# RobotSchematic.net
KiCad netlist of a schematic drawn in EasyEDA
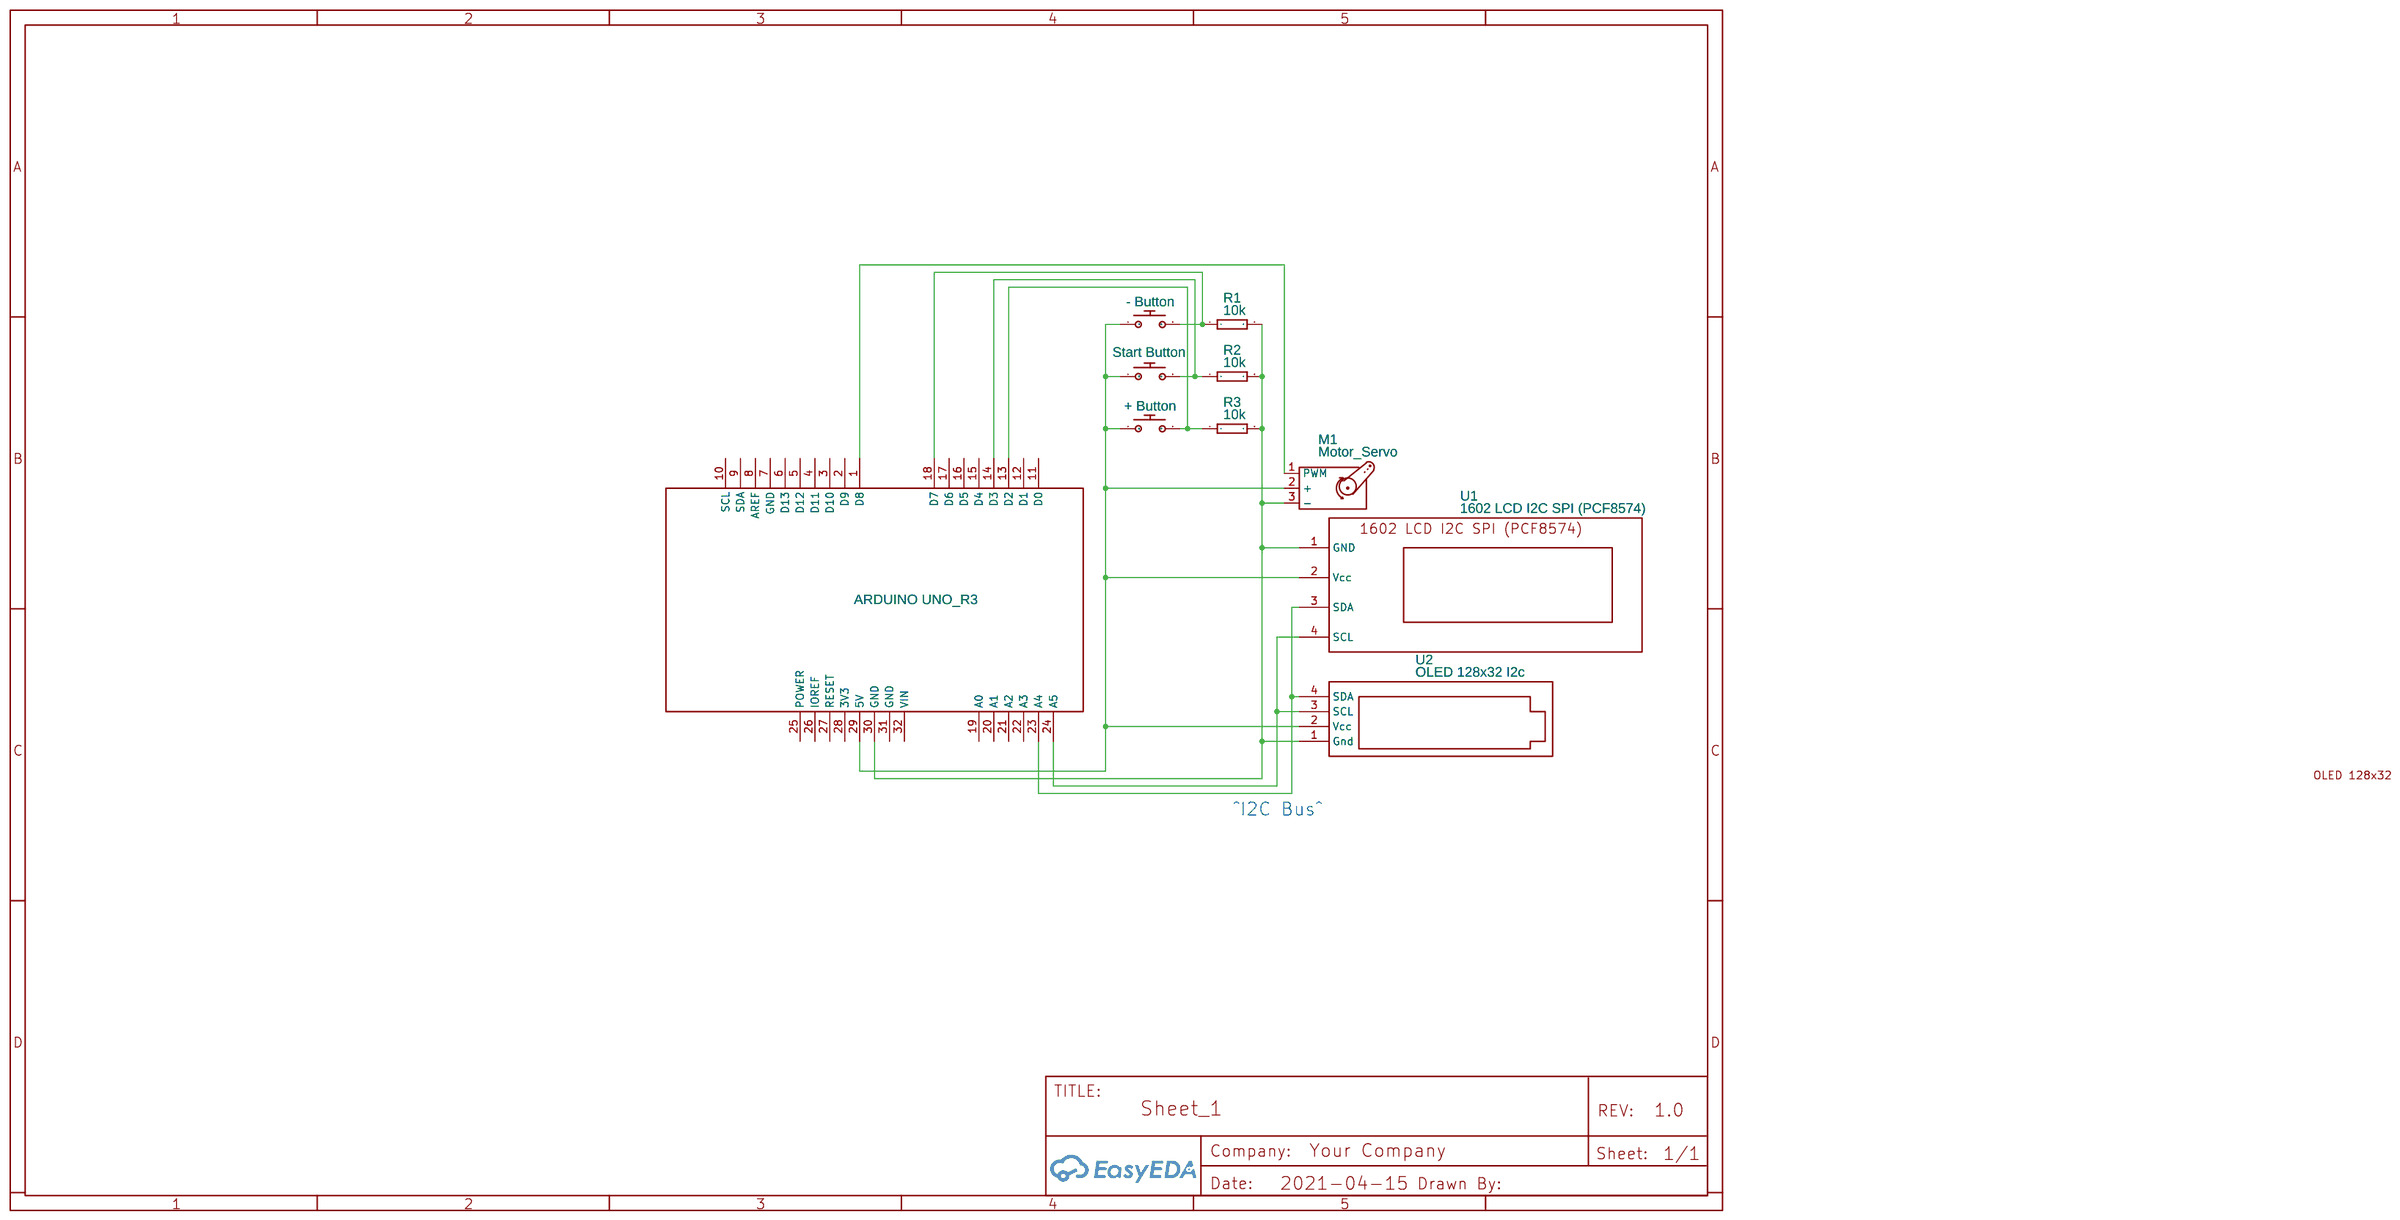
[diagram p0: schematic sheet]

(export (version "E")
  (design (tool "Eeschema 10.0.6"))
  (components
    (comp (ref "M1") (value "Motor_Servo") (libsource (lib "") (part "Motor_Servo")))
    (comp (ref "P1") (value "ARDUINO UNO_R3") (libsource (lib "") (part "UNO_R3")))
    (comp (ref "R1") (value "10k") (libsource (lib "") (part "RESISTOR")))
    (comp (ref "R2") (value "10k") (libsource (lib "") (part "RESISTOR")))
    (comp (ref "R3") (value "10k") (libsource (lib "") (part "RESISTOR")))
    (comp (ref "SW-1SWITCH")
      (value "- Button")
      (fields (field (name "BOM_Supplier Part") "COM-08720"))
      (libsource (lib "") (part "Push Button_2"))
    )
    (comp (ref "SW-2SWITCH")
      (value "Start Button")
      (fields (field (name "BOM_Supplier Part") "COM-08720"))
      (libsource (lib "") (part "Push Button_1"))
    )
    (comp (ref "SW-3SWITCH")
      (value "+ Button")
      (fields (field (name "BOM_Supplier Part") "COM-08720"))
      (libsource (lib "") (part "Push Button"))
    )
    (comp (ref "U1")
      (value "1602 LCD I2C SPI (PCF8574)")
      (libsource (lib "") (part "1602 LCD I2C SPI (PCF8574)"))
    )
    (comp (ref "U2") (value "OLED 128x32 I2c") (libsource (lib "") (part "OLED 128x32 I2c")))
  )
  (nets
    (net (code "1") (name "Net-(M1-+)") (class "Default")
      (node (ref "M1") (pin "2") (pinfunction "+_2") (pintype "unspecified"))
      (node (ref "P1") (pin "29") (pinfunction "5V_29") (pintype "unspecified"))
      (node (ref "SW-1SWITCH") (pin "1") (pinfunction "P$1_1") (pintype "unspecified"))
      (node (ref "SW-2SWITCH") (pin "1") (pinfunction "P$1_1") (pintype "unspecified"))
      (node (ref "SW-3SWITCH") (pin "1") (pinfunction "P$1_1") (pintype "unspecified"))
      (node (ref "U1") (pin "2") (pinfunction "Vcc_2") (pintype "unspecified"))
      (node (ref "U2") (pin "2") (pinfunction "Vcc_2") (pintype "unspecified"))
    )
    (net (code "2") (name "Net-(M1--)") (class "Default")
      (node (ref "M1") (pin "3") (pinfunction "-_3") (pintype "unspecified"))
      (node (ref "P1") (pin "30") (pinfunction "GND_30") (pintype "unspecified"))
      (node (ref "R1") (pin "2") (pinfunction "2_2") (pintype "unspecified"))
      (node (ref "R2") (pin "2") (pinfunction "2_2") (pintype "unspecified"))
      (node (ref "R3") (pin "2") (pinfunction "2_2") (pintype "unspecified"))
      (node (ref "U1") (pin "1") (pinfunction "GND_1") (pintype "unspecified"))
      (node (ref "U2") (pin "1") (pinfunction "Gnd_1") (pintype "unspecified"))
    )
    (net (code "3") (name "Net-(M1-PWM)") (class "Default")
      (node (ref "M1") (pin "1") (pinfunction "PWM_1") (pintype "unspecified"))
      (node (ref "P1") (pin "1") (pinfunction "D8_1") (pintype "unspecified"))
    )
    (net (code "4") (name "Net-(P1-A4)") (class "Default")
      (node (ref "P1") (pin "23") (pinfunction "A4_23") (pintype "unspecified"))
      (node (ref "U1") (pin "3") (pinfunction "SDA_3") (pintype "unspecified"))
      (node (ref "U2") (pin "4") (pinfunction "SDA_4") (pintype "unspecified"))
    )
    (net (code "5") (name "Net-(P1-A5)") (class "Default")
      (node (ref "P1") (pin "24") (pinfunction "A5_24") (pintype "unspecified"))
      (node (ref "U1") (pin "4") (pinfunction "SCL_4") (pintype "unspecified"))
      (node (ref "U2") (pin "3") (pinfunction "SCL_3") (pintype "unspecified"))
    )
    (net (code "6") (name "Net-(P1-D2)") (class "Default")
      (node (ref "P1") (pin "13") (pinfunction "D2_13") (pintype "unspecified"))
      (node (ref "R3") (pin "1") (pinfunction "1_1") (pintype "unspecified"))
      (node (ref "SW-3SWITCH") (pin "2") (pinfunction "P$2_2") (pintype "unspecified"))
    )
    (net (code "7") (name "Net-(P1-D3)") (class "Default")
      (node (ref "P1") (pin "14") (pinfunction "D3_14") (pintype "unspecified"))
      (node (ref "R2") (pin "1") (pinfunction "1_1") (pintype "unspecified"))
      (node (ref "SW-2SWITCH") (pin "2") (pinfunction "P$2_2") (pintype "unspecified"))
    )
    (net (code "8") (name "Net-(P1-D7)") (class "Default")
      (node (ref "P1") (pin "18") (pinfunction "D7_18") (pintype "unspecified"))
      (node (ref "R1") (pin "1") (pinfunction "1_1") (pintype "unspecified"))
      (node (ref "SW-1SWITCH") (pin "2") (pinfunction "P$2_2") (pintype "unspecified"))
    )
    (net (code "9") (name "unconnected-(P1-3V3-Pad28)") (class "Default")
      (node (ref "P1") (pin "28") (pinfunction "3V3_28") (pintype "unspecified"))
    )
    (net (code "10") (name "unconnected-(P1-A0-Pad19)") (class "Default")
      (node (ref "P1") (pin "19") (pinfunction "A0_19") (pintype "unspecified"))
    )
    (net (code "11") (name "unconnected-(P1-A1-Pad20)") (class "Default")
      (node (ref "P1") (pin "20") (pinfunction "A1_20") (pintype "unspecified"))
    )
    (net (code "12") (name "unconnected-(P1-A2-Pad21)") (class "Default")
      (node (ref "P1") (pin "21") (pinfunction "A2_21") (pintype "unspecified"))
    )
    (net (code "13") (name "unconnected-(P1-A3-Pad22)") (class "Default")
      (node (ref "P1") (pin "22") (pinfunction "A3_22") (pintype "unspecified"))
    )
    (net (code "14") (name "unconnected-(P1-AREF-Pad8)") (class "Default")
      (node (ref "P1") (pin "8") (pinfunction "AREF_8") (pintype "unspecified"))
    )
    (net (code "15") (name "unconnected-(P1-D0-Pad11)") (class "Default")
      (node (ref "P1") (pin "11") (pinfunction "D0_11") (pintype "unspecified"))
    )
    (net (code "16") (name "unconnected-(P1-D1-Pad12)") (class "Default")
      (node (ref "P1") (pin "12") (pinfunction "D1_12") (pintype "unspecified"))
    )
    (net (code "17") (name "unconnected-(P1-D4-Pad15)") (class "Default")
      (node (ref "P1") (pin "15") (pinfunction "D4_15") (pintype "unspecified"))
    )
    (net (code "18") (name "unconnected-(P1-D5-Pad16)") (class "Default")
      (node (ref "P1") (pin "16") (pinfunction "D5_16") (pintype "unspecified"))
    )
    (net (code "19") (name "unconnected-(P1-D6-Pad17)") (class "Default")
      (node (ref "P1") (pin "17") (pinfunction "D6_17") (pintype "unspecified"))
    )
    (net (code "20") (name "unconnected-(P1-D9-Pad2)") (class "Default")
      (node (ref "P1") (pin "2") (pinfunction "D9_2") (pintype "unspecified"))
    )
    (net (code "21") (name "unconnected-(P1-D10-Pad3)") (class "Default")
      (node (ref "P1") (pin "3") (pinfunction "D10_3") (pintype "unspecified"))
    )
    (net (code "22") (name "unconnected-(P1-D11-Pad4)") (class "Default")
      (node (ref "P1") (pin "4") (pinfunction "D11_4") (pintype "unspecified"))
    )
    (net (code "23") (name "unconnected-(P1-D12-Pad5)") (class "Default")
      (node (ref "P1") (pin "5") (pinfunction "D12_5") (pintype "unspecified"))
    )
    (net (code "24") (name "unconnected-(P1-D13-Pad6)") (class "Default")
      (node (ref "P1") (pin "6") (pinfunction "D13_6") (pintype "unspecified"))
    )
    (net (code "25") (name "unconnected-(P1-GND-Pad7)") (class "Default")
      (node (ref "P1") (pin "7") (pinfunction "GND_7") (pintype "unspecified"))
    )
    (net (code "26") (name "unconnected-(P1-GND-Pad31)") (class "Default")
      (node (ref "P1") (pin "31") (pinfunction "GND_31") (pintype "unspecified"))
    )
    (net (code "27") (name "unconnected-(P1-IOREF-Pad26)") (class "Default")
      (node (ref "P1") (pin "26") (pinfunction "IOREF_26") (pintype "unspecified"))
    )
    (net (code "28") (name "unconnected-(P1-POWER-Pad25)") (class "Default")
      (node (ref "P1") (pin "25") (pinfunction "POWER_25") (pintype "unspecified"))
    )
    (net (code "29") (name "unconnected-(P1-RESET-Pad27)") (class "Default")
      (node (ref "P1") (pin "27") (pinfunction "RESET_27") (pintype "unspecified"))
    )
    (net (code "30") (name "unconnected-(P1-SCL-Pad10)") (class "Default")
      (node (ref "P1") (pin "10") (pinfunction "SCL_10") (pintype "unspecified"))
    )
    (net (code "31") (name "unconnected-(P1-SDA-Pad9)") (class "Default")
      (node (ref "P1") (pin "9") (pinfunction "SDA_9") (pintype "unspecified"))
    )
    (net (code "32") (name "unconnected-(P1-VIN-Pad32)") (class "Default")
      (node (ref "P1") (pin "32") (pinfunction "VIN_32") (pintype "unspecified"))
    )
  )
)
